# BeaconKeyer_RevA.net
KiCad netlist of a schematic drawn in EAGLE
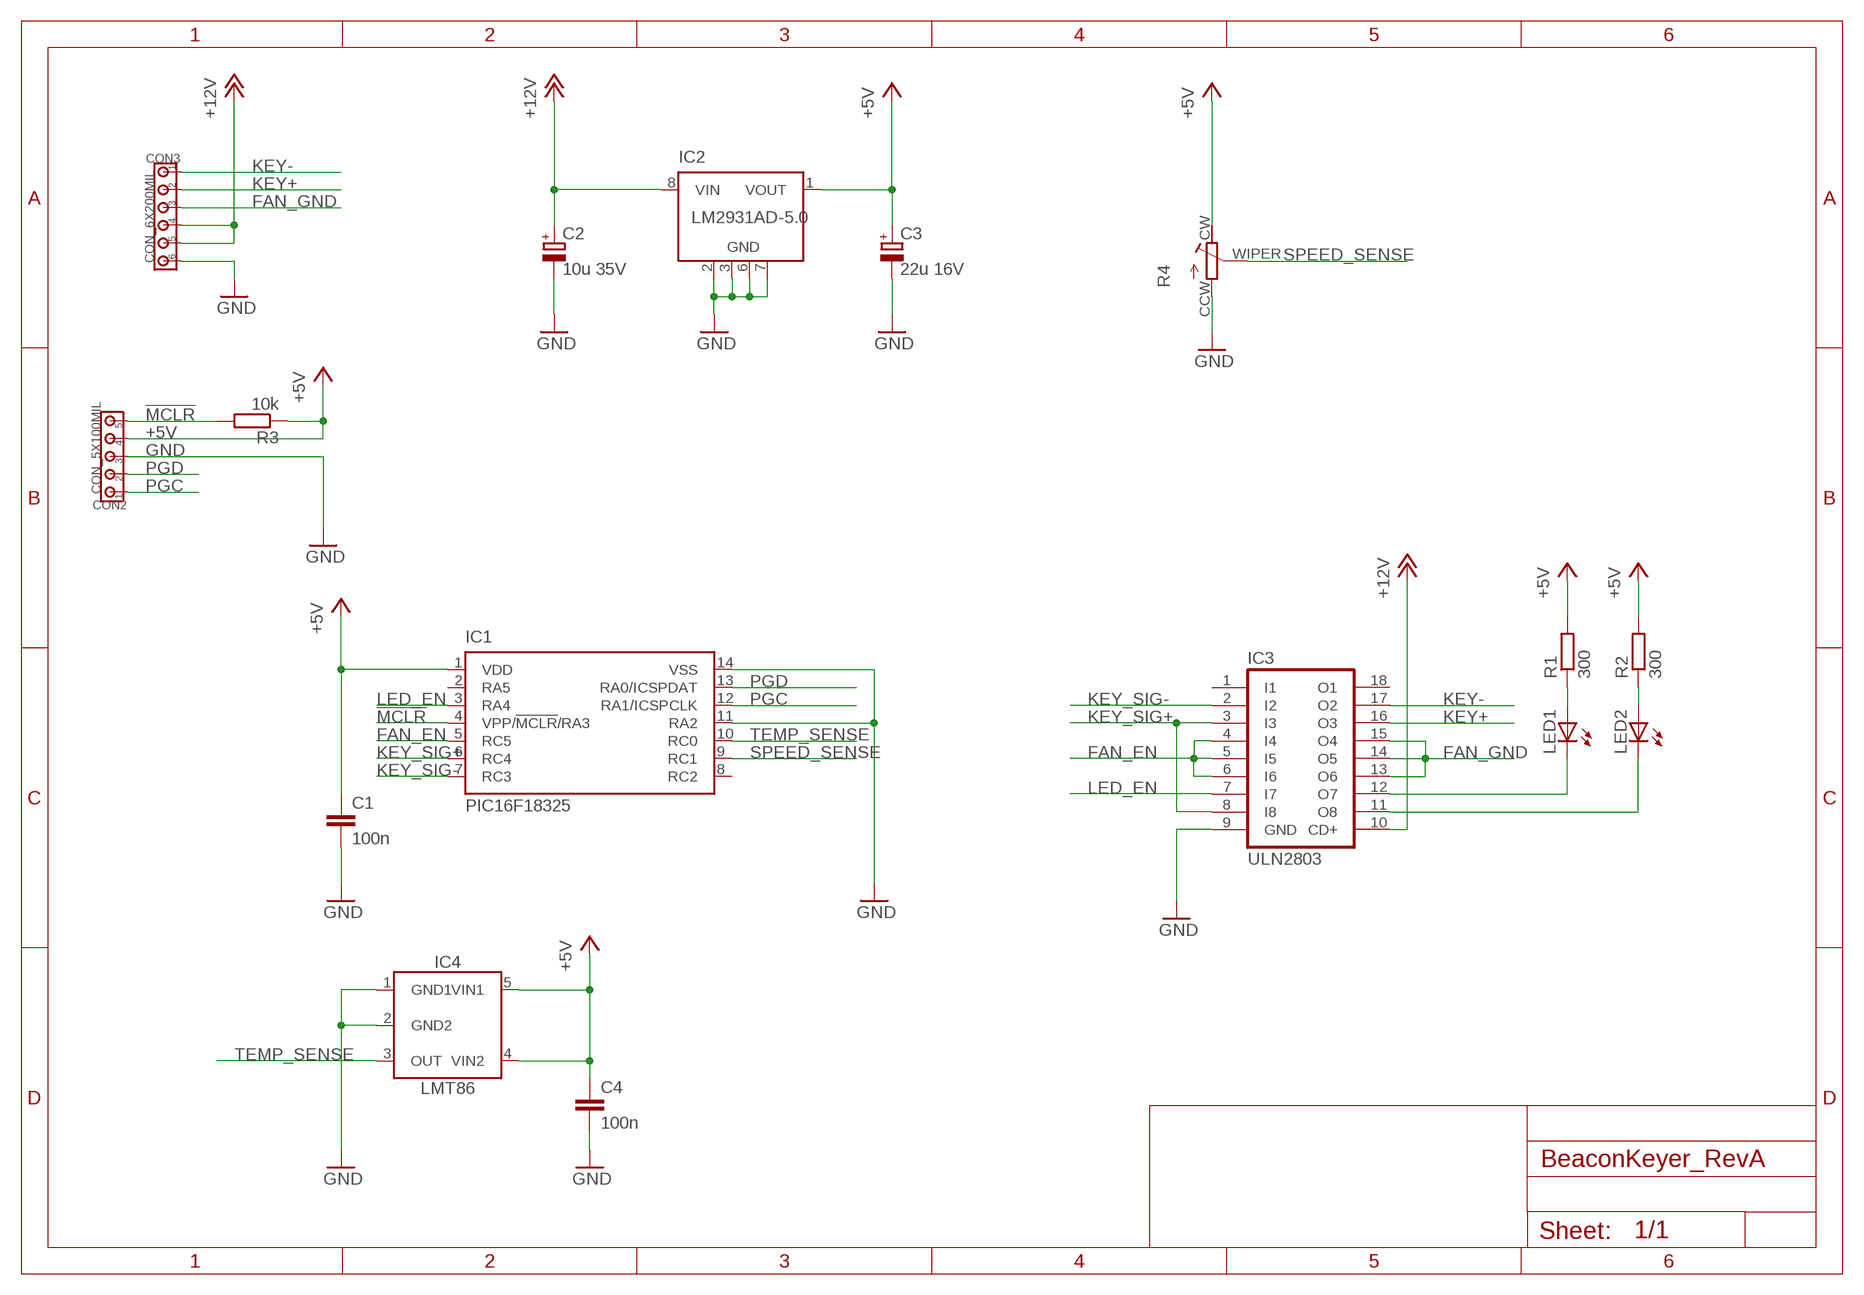
[diagram p0: schematic, sheet 1]

(export (version "E")
  (design (tool "Eeschema 10.0.6"))
  (components
    (comp (ref "C1")
      (value "100n")
      (footprint "eagle-import:C0805")
      (libsource (lib "eagle-import") (part "CC0805"))
    )
    (comp (ref "C2")
      (value "10u 35V")
      (footprint "eagle-import:SMC_C")
      (libsource (lib "eagle-import") (part "C_POLARIZEDSMC_C"))
    )
    (comp (ref "C3")
      (value "22u 16V")
      (footprint "eagle-import:SMC_C")
      (libsource (lib "eagle-import") (part "C_POLARIZEDSMC_C"))
    )
    (comp (ref "C4")
      (value "100n")
      (footprint "eagle-import:C0805")
      (libsource (lib "eagle-import") (part "CC0805"))
    )
    (comp (ref "CON2")
      (value "CON_5X100MIL")
      (footprint "eagle-import:100MIL_5X")
      (libsource (lib "eagle-import") (part "CON_5X100MIL"))
    )
    (comp (ref "CON3")
      (value "CON_6X200MIL")
      (footprint "eagle-import:200MIL_6X")
      (libsource (lib "eagle-import") (part "CON_6X200MIL"))
    )
    (comp (ref "IC1")
      (value "PIC16F18325")
      (footprint "eagle-import:SO14")
      (libsource (lib "eagle-import") (part "PIC16F18325"))
    )
    (comp (ref "IC2")
      (value "LM2931AD-5.0")
      (footprint "eagle-import:SOIC8")
      (libsource (lib "eagle-import") (part "LM2931AD-5.0"))
    )
    (comp (ref "IC3")
      (value "ULN2803")
      (footprint "eagle-import:SO18W")
      (libsource (lib "eagle-import") (part "ULN2803"))
    )
    (comp (ref "IC4")
      (value "LMT86")
      (footprint "eagle-import:SC70-5")
      (libsource (lib "eagle-import") (part "LMT86"))
    )
    (comp (ref "LED1")
      (value "LED0805")
      (footprint "eagle-import:LED0805")
      (libsource (lib "eagle-import") (part "LED0805"))
    )
    (comp (ref "LED2")
      (value "LED0805")
      (footprint "eagle-import:LED0805")
      (libsource (lib "eagle-import") (part "LED0805"))
    )
    (comp (ref "R1")
      (value "300")
      (footprint "eagle-import:R0805")
      (libsource (lib "eagle-import") (part "RESISTORR0805"))
    )
    (comp (ref "R2")
      (value "300")
      (footprint "eagle-import:R0805")
      (libsource (lib "eagle-import") (part "RESISTORR0805"))
    )
    (comp (ref "R3")
      (value "10k")
      (footprint "eagle-import:R0805")
      (libsource (lib "eagle-import") (part "RESISTORR0805"))
    )
    (comp (ref "R4")
      (value "TRIMMER3314G")
      (footprint "eagle-import:RTRIM3314G")
      (libsource (lib "eagle-import") (part "TRIMMER3314G"))
    )
  )
  (nets
    (net (code "1") (name "+5V") (class "Default")
      (node (ref "C1") (pin "1") (pinfunction "1_1") (pintype "passive"))
      (node (ref "C3") (pin "+") (pinfunction "+_+") (pintype "passive"))
      (node (ref "C4") (pin "1") (pinfunction "1_1") (pintype "passive"))
      (node (ref "CON2") (pin "4") (pinfunction "4_4") (pintype "passive"))
      (node (ref "IC1") (pin "1") (pinfunction "VDD_1") (pintype "power_in"))
      (node (ref "IC2") (pin "1") (pinfunction "VOUT_1") (pintype "output"))
      (node (ref "IC4") (pin "4") (pinfunction "VIN2_4") (pintype "passive"))
      (node (ref "IC4") (pin "5") (pinfunction "VIN1_5") (pintype "input"))
      (node (ref "R1") (pin "2") (pinfunction "2_2") (pintype "passive"))
      (node (ref "R2") (pin "2") (pinfunction "2_2") (pintype "passive"))
      (node (ref "R3") (pin "1") (pinfunction "1_1") (pintype "passive"))
      (node (ref "R4") (pin "CW") (pinfunction "CW_CW") (pintype "passive"))
    )
    (net (code "2") (name "+12V") (class "Default")
      (node (ref "C2") (pin "+") (pinfunction "+_+") (pintype "passive"))
      (node (ref "CON3") (pin "4") (pinfunction "4_4") (pintype "passive"))
      (node (ref "CON3") (pin "5") (pinfunction "5_5") (pintype "passive"))
      (node (ref "IC2") (pin "8") (pinfunction "VIN_8") (pintype "passive"))
      (node (ref "IC3") (pin "10") (pinfunction "CD+_10") (pintype "passive"))
    )
    (net (code "3") (name "/FAN_EN") (class "Default")
      (node (ref "IC1") (pin "5") (pinfunction "RC5_5") (pintype "bidirectional"))
      (node (ref "IC3") (pin "4") (pinfunction "I4_4") (pintype "input"))
      (node (ref "IC3") (pin "5") (pinfunction "I5_5") (pintype "input"))
      (node (ref "IC3") (pin "6") (pinfunction "I6_6") (pintype "input"))
    )
    (net (code "4") (name "/FAN_GND") (class "Default")
      (node (ref "CON3") (pin "3") (pinfunction "3_3") (pintype "passive"))
      (node (ref "IC3") (pin "13") (pinfunction "O6_13") (pintype "open_collector"))
      (node (ref "IC3") (pin "14") (pinfunction "O5_14") (pintype "open_collector"))
      (node (ref "IC3") (pin "15") (pinfunction "O4_15") (pintype "open_collector"))
    )
    (net (code "5") (name "/KEY+") (class "Default")
      (node (ref "CON3") (pin "2") (pinfunction "2_2") (pintype "passive"))
      (node (ref "IC3") (pin "16") (pinfunction "O3_16") (pintype "open_collector"))
    )
    (net (code "6") (name "/KEY-") (class "Default")
      (node (ref "CON3") (pin "1") (pinfunction "1_1") (pintype "passive"))
      (node (ref "IC3") (pin "17") (pinfunction "O2_17") (pintype "open_collector"))
    )
    (net (code "7") (name "/KEY_SIG+") (class "Default")
      (node (ref "IC1") (pin "6") (pinfunction "RC4_6") (pintype "bidirectional"))
      (node (ref "IC3") (pin "3") (pinfunction "I3_3") (pintype "input"))
      (node (ref "IC3") (pin "8") (pinfunction "I8_8") (pintype "input"))
    )
    (net (code "8") (name "/KEY_SIG-") (class "Default")
      (node (ref "IC1") (pin "7") (pinfunction "RC3_7") (pintype "bidirectional"))
      (node (ref "IC3") (pin "2") (pinfunction "I2_2") (pintype "input"))
    )
    (net (code "9") (name "/LED_EN") (class "Default")
      (node (ref "IC1") (pin "3") (pinfunction "RA4_3") (pintype "bidirectional"))
      (node (ref "IC3") (pin "7") (pinfunction "I7_7") (pintype "input"))
    )
    (net (code "10") (name "/PGC") (class "Default")
      (node (ref "CON2") (pin "1") (pinfunction "1_1") (pintype "passive"))
      (node (ref "IC1") (pin "12") (pinfunction "RA1/ICSPCLK_12") (pintype "bidirectional"))
    )
    (net (code "11") (name "/PGD") (class "Default")
      (node (ref "CON2") (pin "2") (pinfunction "2_2") (pintype "passive"))
      (node (ref "IC1") (pin "13") (pinfunction "RA0/ICSPDAT_13") (pintype "bidirectional"))
    )
    (net (code "12") (name "/SPEED_SENSE") (class "Default")
      (node (ref "IC1") (pin "9") (pinfunction "RC1_9") (pintype "bidirectional"))
      (node (ref "R4") (pin "WIPER") (pinfunction "WIPER_WIPER") (pintype "passive"))
    )
    (net (code "13") (name "/TEMP_SENSE") (class "Default")
      (node (ref "IC1") (pin "10") (pinfunction "RC0_10") (pintype "bidirectional"))
      (node (ref "IC4") (pin "3") (pinfunction "OUT_3") (pintype "input"))
    )
    (net (code "14") (name "/~{MCLR}") (class "Default")
      (node (ref "CON2") (pin "5") (pinfunction "5_5") (pintype "passive"))
      (node (ref "IC1") (pin "4") (pinfunction "VPP/~{MCLR}/RA3_4") (pintype "bidirectional"))
      (node (ref "R3") (pin "2") (pinfunction "2_2") (pintype "passive"))
    )
    (net (code "15") (name "GND") (class "Default")
      (node (ref "C1") (pin "2") (pinfunction "2_2") (pintype "passive"))
      (node (ref "C2") (pin "-") (pinfunction "-_-") (pintype "passive"))
      (node (ref "C3") (pin "-") (pinfunction "-_-") (pintype "passive"))
      (node (ref "C4") (pin "2") (pinfunction "2_2") (pintype "passive"))
      (node (ref "CON2") (pin "3") (pinfunction "3_3") (pintype "passive"))
      (node (ref "CON3") (pin "6") (pinfunction "6_6") (pintype "passive"))
      (node (ref "IC1") (pin "11") (pinfunction "RA2_11") (pintype "bidirectional"))
      (node (ref "IC1") (pin "14") (pinfunction "VSS_14") (pintype "power_in"))
      (node (ref "IC2") (pin "2") (pinfunction "GND_2") (pintype "power_in"))
      (node (ref "IC2") (pin "3") (pinfunction "GND_3") (pintype "power_in"))
      (node (ref "IC2") (pin "6") (pinfunction "GND_6") (pintype "power_in"))
      (node (ref "IC2") (pin "7") (pinfunction "GND_7") (pintype "power_in"))
      (node (ref "IC3") (pin "9") (pinfunction "GND_9") (pintype "power_in"))
      (node (ref "IC4") (pin "1") (pinfunction "GND1_1") (pintype "power_in"))
      (node (ref "IC4") (pin "2") (pinfunction "GND2_2") (pintype "power_in"))
      (node (ref "R4") (pin "CCW") (pinfunction "CCW_CCW") (pintype "passive"))
    )
    (net (code "16") (name "Net-(IC3-O7)") (class "Default")
      (node (ref "IC3") (pin "12") (pinfunction "O7_12") (pintype "open_collector"))
      (node (ref "LED1") (pin "C") (pinfunction "C_C") (pintype "passive"))
    )
    (net (code "17") (name "Net-(IC3-O8)") (class "Default")
      (node (ref "IC3") (pin "11") (pinfunction "O8_11") (pintype "open_collector"))
      (node (ref "LED2") (pin "C") (pinfunction "C_C") (pintype "passive"))
    )
    (net (code "18") (name "Net-(LED1-PadA)") (class "Default")
      (node (ref "LED1") (pin "A") (pinfunction "A_A") (pintype "passive"))
      (node (ref "R1") (pin "1") (pinfunction "1_1") (pintype "passive"))
    )
    (net (code "19") (name "Net-(LED2-PadA)") (class "Default")
      (node (ref "LED2") (pin "A") (pinfunction "A_A") (pintype "passive"))
      (node (ref "R2") (pin "1") (pinfunction "1_1") (pintype "passive"))
    )
    (net (code "20") (name "unconnected-(IC1-RA5-Pad2)") (class "Default")
      (node (ref "IC1") (pin "2") (pinfunction "RA5_2") (pintype "input"))
    )
    (net (code "21") (name "unconnected-(IC1-RC2-Pad8)") (class "Default")
      (node (ref "IC1") (pin "8") (pinfunction "RC2_8") (pintype "bidirectional"))
    )
    (net (code "22") (name "unconnected-(IC3-I1-Pad1)") (class "Default")
      (node (ref "IC3") (pin "1") (pinfunction "I1_1") (pintype "input"))
    )
    (net (code "23") (name "unconnected-(IC3-O1-Pad18)") (class "Default")
      (node (ref "IC3") (pin "18") (pinfunction "O1_18") (pintype "open_collector"))
    )
  )
)
